# ME433Schematic.net
KiCad netlist of a schematic drawn in EAGLE
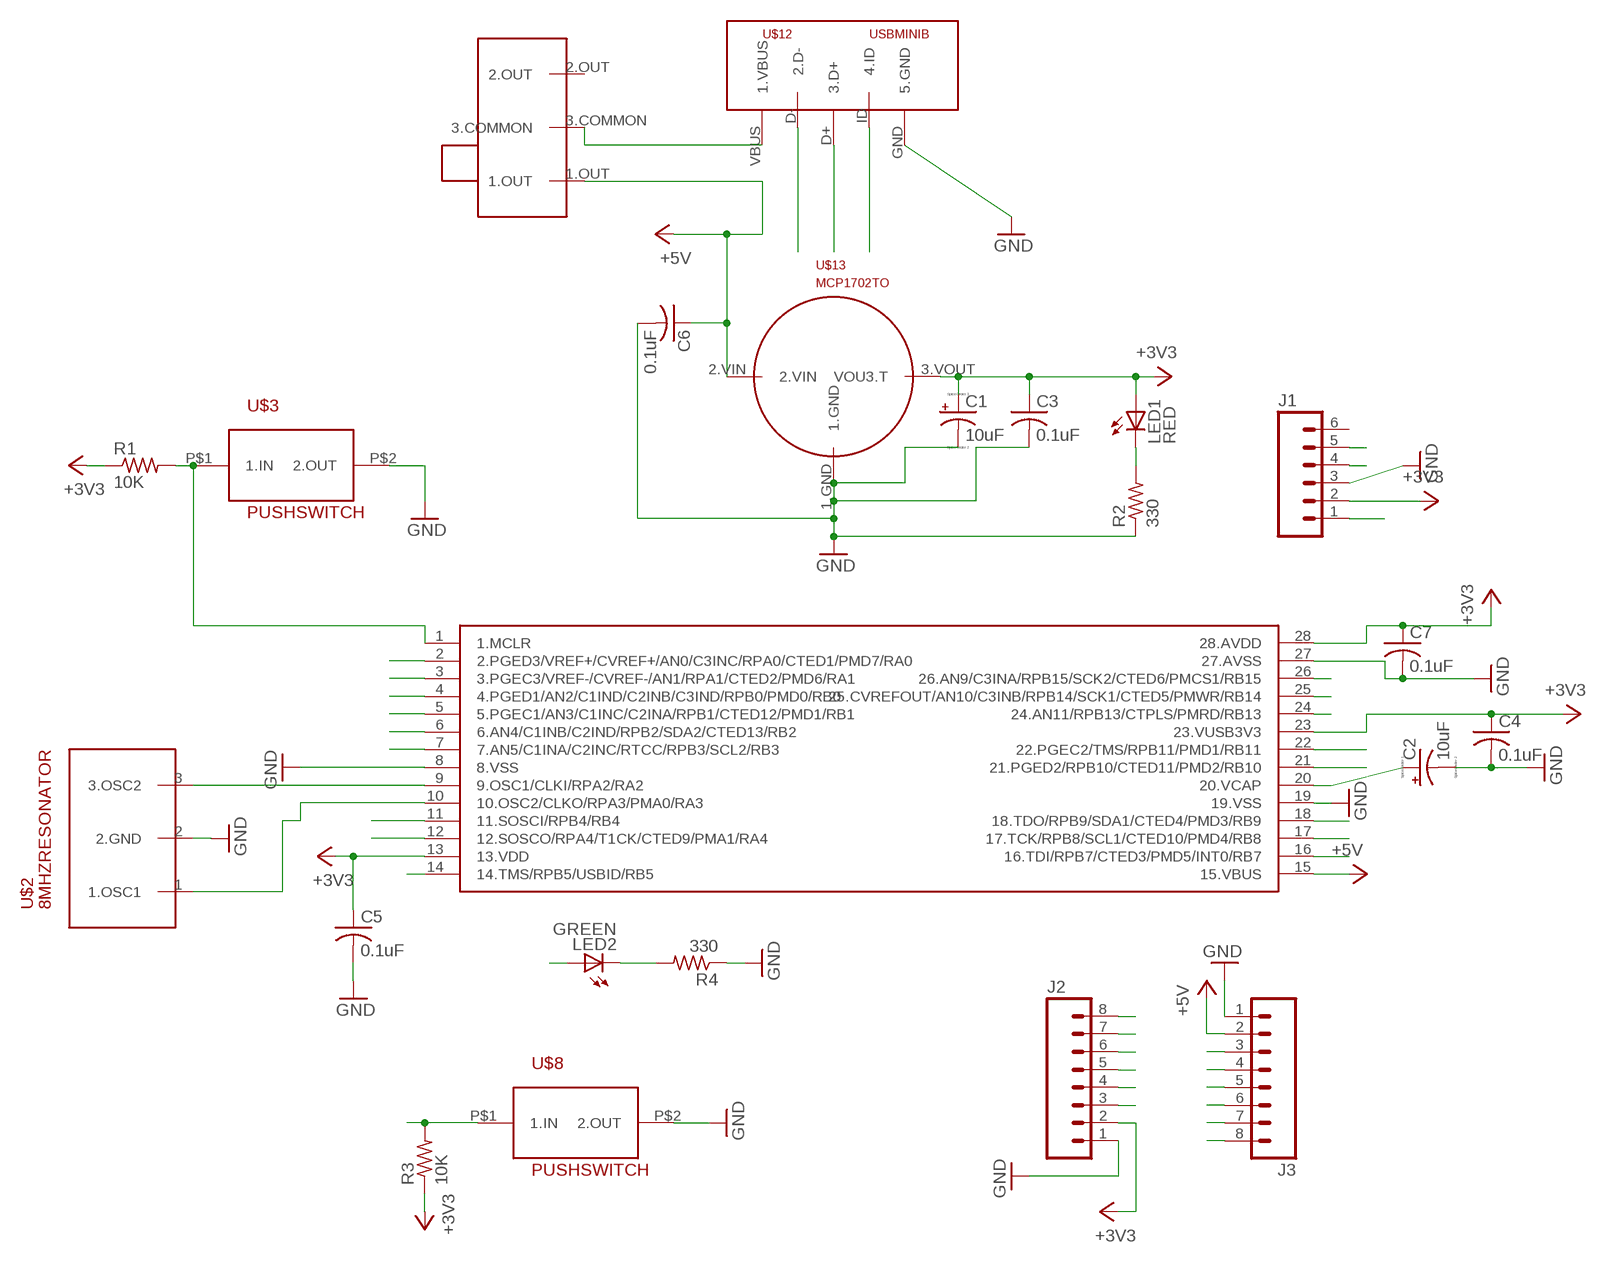
[diagram p0: schematic, sheet 1]

(export (version "E")
  (design (tool "Eeschema 10.0.6"))
  (components
    (comp (ref "C1")
      (value "10uF")
      (footprint "eagle-import:B45181B")
      (libsource (lib "eagle-import") (part "CPOL-USB45181B"))
    )
    (comp (ref "C2")
      (value "10uF")
      (footprint "eagle-import:B45181B")
      (libsource (lib "eagle-import") (part "CPOL-USB45181B"))
    )
    (comp (ref "C3")
      (value "0.1uF")
      (footprint "eagle-import:C025-025X050")
      (libsource (lib "eagle-import") (part "C-US025-025X050"))
    )
    (comp (ref "C4")
      (value "0.1uF")
      (footprint "eagle-import:C025-025X050")
      (libsource (lib "eagle-import") (part "C-US025-025X050"))
    )
    (comp (ref "C5")
      (value "0.1uF")
      (footprint "eagle-import:C025-025X050")
      (libsource (lib "eagle-import") (part "C-US025-025X050"))
    )
    (comp (ref "C6")
      (value "0.1uF")
      (footprint "eagle-import:C025-025X050")
      (libsource (lib "eagle-import") (part "C-US025-025X050"))
    )
    (comp (ref "C7")
      (value "0.1uF")
      (footprint "eagle-import:C025-030X050")
      (libsource (lib "eagle-import") (part "C-US025-030X050"))
    )
    (comp (ref "J1")
      (value "M06SILK_FEMALE_PTH")
      (footprint "eagle-import:1X06")
      (libsource (lib "eagle-import") (part "M06SILK_FEMALE_PTH"))
    )
    (comp (ref "J2")
      (value "M08")
      (footprint "eagle-import:1X08_ROUND")
      (libsource (lib "eagle-import") (part "M08"))
    )
    (comp (ref "J3")
      (value "M08")
      (footprint "eagle-import:1X08_ROUND")
      (libsource (lib "eagle-import") (part "M08"))
    )
    (comp (ref "LED1")
      (value "RED")
      (footprint "eagle-import:LED3MM")
      (libsource (lib "eagle-import") (part "LED3MM"))
    )
    (comp (ref "LED2")
      (value "GREEN")
      (footprint "eagle-import:LED3MM")
      (libsource (lib "eagle-import") (part "LED3MM"))
    )
    (comp (ref "R1")
      (value "10K")
      (footprint "eagle-import:0207_10")
      (libsource (lib "eagle-import") (part "R-US_0207/10"))
    )
    (comp (ref "R2")
      (value "330")
      (footprint "eagle-import:0207_10")
      (libsource (lib "eagle-import") (part "R-US_0207/10"))
    )
    (comp (ref "R3")
      (value "10K")
      (footprint "eagle-import:0207_10")
      (libsource (lib "eagle-import") (part "R-US_0207/10"))
    )
    (comp (ref "R4")
      (value "330")
      (footprint "eagle-import:0207_10")
      (libsource (lib "eagle-import") (part "R-US_0207/10"))
    )
    (comp (ref "U$1")
      (value "PIC32MX250F128B")
      (footprint "eagle-import:DIL28-3")
      (libsource (lib "eagle-import") (part "PIC32MX250F128B"))
    )
    (comp (ref "U$2")
      (value "8MHZRESONATOR")
      (footprint "eagle-import:1X03")
      (libsource (lib "eagle-import") (part "8MHZRESONATOR"))
    )
    (comp (ref "U$3")
      (value "PUSHSWITCH")
      (footprint "eagle-import:SWITCH")
      (libsource (lib "eagle-import") (part "PUSHSWITCH"))
    )
    (comp (ref "U$8")
      (value "PUSHSWITCH")
      (footprint "eagle-import:SWITCH")
      (libsource (lib "eagle-import") (part "PUSHSWITCH"))
    )
    (comp (ref "U$12")
      (value "USBMINIB")
      (footprint "eagle-import:USB-MB-H")
      (libsource (lib "eagle-import") (part "USBMINIB"))
    )
    (comp (ref "U$13")
      (value "MCP1702TO")
      (footprint "eagle-import:TO92")
      (libsource (lib "eagle-import") (part "MCP1702TO"))
    )
    (comp (ref "U$18")
      (value "SLIDESWITCH")
      (footprint "eagle-import:SPDTSLIDE")
      (libsource (lib "eagle-import") (part "SLIDESWITCH"))
    )
  )
  (nets
    (net (code "1") (name "+3V3") (class "Default")
      (node (ref "C1") (pin "+") (pinfunction "+_+") (pintype "passive"))
      (node (ref "C3") (pin "1") (pinfunction "1_1") (pintype "passive"))
      (node (ref "C4") (pin "1") (pinfunction "1_1") (pintype "passive"))
      (node (ref "C5") (pin "1") (pinfunction "1_1") (pintype "passive"))
      (node (ref "C7") (pin "1") (pinfunction "1_1") (pintype "passive"))
      (node (ref "J1") (pin "2") (pinfunction "2_2") (pintype "passive"))
      (node (ref "J2") (pin "2") (pinfunction "2_2") (pintype "passive"))
      (node (ref "LED1") (pin "A") (pinfunction "1.+_A") (pintype "passive"))
      (node (ref "R1") (pin "1") (pinfunction "1_1") (pintype "passive"))
      (node (ref "R3") (pin "1") (pinfunction "1_1") (pintype "passive"))
      (node (ref "U$1") (pin "13") (pinfunction "13.VDD_13") (pintype "bidirectional"))
      (node (ref "U$1") (pin "23") (pinfunction "23.VUSB3V3_23") (pintype "bidirectional"))
      (node (ref "U$1") (pin "28") (pinfunction "28.AVDD_28") (pintype "bidirectional"))
      (node (ref "U$13") (pin "3.VOUT") (pinfunction "VOU3.T_3.VOUT") (pintype "bidirectional"))
    )
    (net (code "2") (name "+5V") (class "Default")
      (node (ref "C6") (pin "1") (pinfunction "1_1") (pintype "passive"))
      (node (ref "J3") (pin "2") (pinfunction "2_2") (pintype "passive"))
      (node (ref "U$1") (pin "15") (pinfunction "15.VBUS_15") (pintype "bidirectional"))
      (node (ref "U$13") (pin "2.VIN") (pinfunction "2.VIN_2.VIN") (pintype "bidirectional"))
      (node (ref "U$18") (pin "1.OUT") (pinfunction "1.OUT_1.OUT") (pintype "bidirectional"))
    )
    (net (code "3") (name "/A0") (class "Default")
      (node (ref "J2") (pin "8") (pinfunction "8_8") (pintype "passive"))
      (node (ref "U$1") (pin "2") (pinfunction "2.PGED3/VREF+/CVREF+/AN0/C3INC/RPA0/CTED1/PMD7/RA0_2") (pintype "bidirectional"))
    )
    (net (code "4") (name "/A1") (class "Default")
      (node (ref "J2") (pin "7") (pinfunction "7_7") (pintype "passive"))
      (node (ref "U$1") (pin "3") (pinfunction "3.PGEC3/VREF-/CVREF-/AN1/RPA1/CTED2/PMD6/RA1_3") (pintype "bidirectional"))
    )
    (net (code "5") (name "/A4") (class "Default")
      (node (ref "J2") (pin "3") (pinfunction "3_3") (pintype "passive"))
      (node (ref "LED2") (pin "A") (pinfunction "1.+_A") (pintype "passive"))
      (node (ref "U$1") (pin "12") (pinfunction "12.SOSCO/RPA4/T1CK/CTED9/PMA1/RA4_12") (pintype "bidirectional"))
    )
    (net (code "6") (name "/B2") (class "Default")
      (node (ref "J2") (pin "6") (pinfunction "6_6") (pintype "passive"))
      (node (ref "U$1") (pin "6") (pinfunction "6.AN4/C1INB/C2IND/RPB2/SDA2/CTED13/RB2_6") (pintype "bidirectional"))
    )
    (net (code "7") (name "/B3") (class "Default")
      (node (ref "J2") (pin "5") (pinfunction "5_5") (pintype "passive"))
      (node (ref "U$1") (pin "7") (pinfunction "7.AN5/C1INA/C2INC/RTCC/RPB3/SCL2/RB3_7") (pintype "bidirectional"))
    )
    (net (code "8") (name "/B4") (class "Default")
      (node (ref "J2") (pin "4") (pinfunction "4_4") (pintype "passive"))
      (node (ref "R3") (pin "2") (pinfunction "2_2") (pintype "passive"))
      (node (ref "U$1") (pin "11") (pinfunction "11.SOSCI/RPB4/RB4_11") (pintype "bidirectional"))
      (node (ref "U$8") (pin "P$1") (pinfunction "1.IN_P$1") (pintype "bidirectional"))
    )
    (net (code "9") (name "/B7") (class "Default")
      (node (ref "J3") (pin "3") (pinfunction "3_3") (pintype "passive"))
      (node (ref "U$1") (pin "16") (pinfunction "16.TDI/RPB7/CTED3/PMD5/INT0/RB7_16") (pintype "bidirectional"))
    )
    (net (code "10") (name "/B8") (class "Default")
      (node (ref "J3") (pin "4") (pinfunction "4_4") (pintype "passive"))
      (node (ref "U$1") (pin "17") (pinfunction "17.TCK/RPB8/SCL1/CTED10/PMD4/RB8_17") (pintype "bidirectional"))
    )
    (net (code "11") (name "/B9") (class "Default")
      (node (ref "J3") (pin "5") (pinfunction "5_5") (pintype "passive"))
      (node (ref "U$1") (pin "18") (pinfunction "18.TDO/RPB9/SDA1/CTED4/PMD3/RB9_18") (pintype "bidirectional"))
    )
    (net (code "12") (name "/B13") (class "Default")
      (node (ref "J3") (pin "6") (pinfunction "6_6") (pintype "passive"))
      (node (ref "U$1") (pin "24") (pinfunction "24.AN11/RPB13/CTPLS/PMRD/RB13_24") (pintype "bidirectional"))
    )
    (net (code "13") (name "/B14") (class "Default")
      (node (ref "J3") (pin "7") (pinfunction "7_7") (pintype "passive"))
      (node (ref "U$1") (pin "25") (pinfunction "25.CVREFOUT/AN10/C3INB/RPB14/SCK1/CTED5/PMWR/RB14_25") (pintype "bidirectional"))
    )
    (net (code "14") (name "/B15") (class "Default")
      (node (ref "J3") (pin "8") (pinfunction "8_8") (pintype "passive"))
      (node (ref "U$1") (pin "26") (pinfunction "26.AN9/C3INA/RPB15/SCK2/CTED6/PMCS1/RB15_26") (pintype "bidirectional"))
    )
    (net (code "15") (name "/D+") (class "Default")
      (node (ref "U$1") (pin "21") (pinfunction "21.PGED2/RPB10/CTED11/PMD2/RB10_21") (pintype "bidirectional"))
      (node (ref "U$12") (pin "D+") (pinfunction "3.D+_D+") (pintype "bidirectional"))
    )
    (net (code "16") (name "/D-") (class "Default")
      (node (ref "U$1") (pin "22") (pinfunction "22.PGEC2/TMS/RPB11/PMD1/RB11_22") (pintype "bidirectional"))
      (node (ref "U$12") (pin "D-") (pinfunction "2.D-_D-") (pintype "bidirectional"))
    )
    (net (code "17") (name "/ID") (class "Default")
      (node (ref "U$1") (pin "14") (pinfunction "14.TMS/RPB5/USBID/RB5_14") (pintype "bidirectional"))
      (node (ref "U$12") (pin "ID") (pinfunction "4.ID_ID") (pintype "bidirectional"))
    )
    (net (code "18") (name "/MCLR") (class "Default")
      (node (ref "J1") (pin "1") (pinfunction "1_1") (pintype "passive"))
      (node (ref "R1") (pin "2") (pinfunction "2_2") (pintype "passive"))
      (node (ref "U$1") (pin "1") (pinfunction "1.MCLR_1") (pintype "bidirectional"))
      (node (ref "U$3") (pin "P$1") (pinfunction "1.IN_P$1") (pintype "bidirectional"))
    )
    (net (code "19") (name "/PEGC1") (class "Default")
      (node (ref "J1") (pin "5") (pinfunction "5_5") (pintype "passive"))
      (node (ref "U$1") (pin "5") (pinfunction "5.PGEC1/AN3/C1INC/C2INA/RPB1/CTED12/PMD1/RB1_5") (pintype "bidirectional"))
    )
    (net (code "20") (name "/PEGD1") (class "Default")
      (node (ref "J1") (pin "4") (pinfunction "4_4") (pintype "passive"))
      (node (ref "U$1") (pin "4") (pinfunction "4.PGED1/AN2/C1IND/C2INB/C3IND/RPB0/PMD0/RB0_4") (pintype "bidirectional"))
    )
    (net (code "21") (name "GND") (class "Default")
      (node (ref "C1") (pin "-") (pinfunction "-_-") (pintype "passive"))
      (node (ref "C2") (pin "-") (pinfunction "-_-") (pintype "passive"))
      (node (ref "C3") (pin "2") (pinfunction "2_2") (pintype "passive"))
      (node (ref "C4") (pin "2") (pinfunction "2_2") (pintype "passive"))
      (node (ref "C5") (pin "2") (pinfunction "2_2") (pintype "passive"))
      (node (ref "C6") (pin "2") (pinfunction "2_2") (pintype "passive"))
      (node (ref "C7") (pin "2") (pinfunction "2_2") (pintype "passive"))
      (node (ref "J1") (pin "3") (pinfunction "3_3") (pintype "passive"))
      (node (ref "J2") (pin "1") (pinfunction "1_1") (pintype "passive"))
      (node (ref "J3") (pin "1") (pinfunction "1_1") (pintype "passive"))
      (node (ref "R2") (pin "1") (pinfunction "1_1") (pintype "passive"))
      (node (ref "R4") (pin "1") (pinfunction "1_1") (pintype "passive"))
      (node (ref "U$1") (pin "19") (pinfunction "19.VSS_19") (pintype "bidirectional"))
      (node (ref "U$1") (pin "27") (pinfunction "27.AVSS_27") (pintype "bidirectional"))
      (node (ref "U$1") (pin "8") (pinfunction "8.VSS_8") (pintype "bidirectional"))
      (node (ref "U$12") (pin "GND") (pinfunction "5.GND_GND") (pintype "bidirectional"))
      (node (ref "U$13") (pin "1.GND") (pinfunction "1.GND_1.GND") (pintype "bidirectional"))
      (node (ref "U$2") (pin "2") (pinfunction "2.GND_2") (pintype "bidirectional"))
      (node (ref "U$3") (pin "P$2") (pinfunction "2.OUT_P$2") (pintype "bidirectional"))
      (node (ref "U$8") (pin "P$2") (pinfunction "2.OUT_P$2") (pintype "bidirectional"))
    )
    (net (code "22") (name "Net-(LED1-2.-)") (class "Default")
      (node (ref "LED1") (pin "K") (pinfunction "2.-_K") (pintype "passive"))
      (node (ref "R2") (pin "2") (pinfunction "2_2") (pintype "passive"))
    )
    (net (code "23") (name "Net-(LED2-2.-)") (class "Default")
      (node (ref "LED2") (pin "K") (pinfunction "2.-_K") (pintype "passive"))
      (node (ref "R4") (pin "2") (pinfunction "2_2") (pintype "passive"))
    )
    (net (code "24") (name "Net-(U$1-9.OSC1{slash}CLKI{slash}RPA2{slash}RA2)") (class "Default")
      (node (ref "U$1") (pin "9") (pinfunction "9.OSC1/CLKI/RPA2/RA2_9") (pintype "bidirectional"))
      (node (ref "U$2") (pin "3") (pinfunction "3.OSC2_3") (pintype "bidirectional"))
    )
    (net (code "25") (name "Net-(U$1-10.OSC2{slash}CLKO{slash}RPA3{slash}PMA0{slash}RA3)") (class "Default")
      (node (ref "U$1") (pin "10") (pinfunction "10.OSC2/CLKO/RPA3/PMA0/RA3_10") (pintype "bidirectional"))
      (node (ref "U$2") (pin "1") (pinfunction "1.OSC1_1") (pintype "bidirectional"))
    )
    (net (code "26") (name "Net-(U$1-20.VCAP)") (class "Default")
      (node (ref "C2") (pin "+") (pinfunction "+_+") (pintype "passive"))
      (node (ref "U$1") (pin "20") (pinfunction "20.VCAP_20") (pintype "bidirectional"))
    )
    (net (code "27") (name "Net-(U$12-1.VBUS)") (class "Default")
      (node (ref "U$12") (pin "VBUS") (pinfunction "1.VBUS_VBUS") (pintype "bidirectional"))
      (node (ref "U$18") (pin "3.COMMON") (pinfunction "3.COMMON_3.COMMON") (pintype "bidirectional"))
    )
    (net (code "28") (name "unconnected-(J1-Pad6)") (class "Default")
      (node (ref "J1") (pin "6") (pinfunction "6_6") (pintype "passive"))
    )
    (net (code "29") (name "unconnected-(U$18-Pad2.OUT)") (class "Default")
      (node (ref "U$18") (pin "2.OUT") (pinfunction "2.OUT_2.OUT") (pintype "bidirectional"))
    )
  )
)
